# latch5.net
KiCad netlist of a schematic drawn in EAGLE
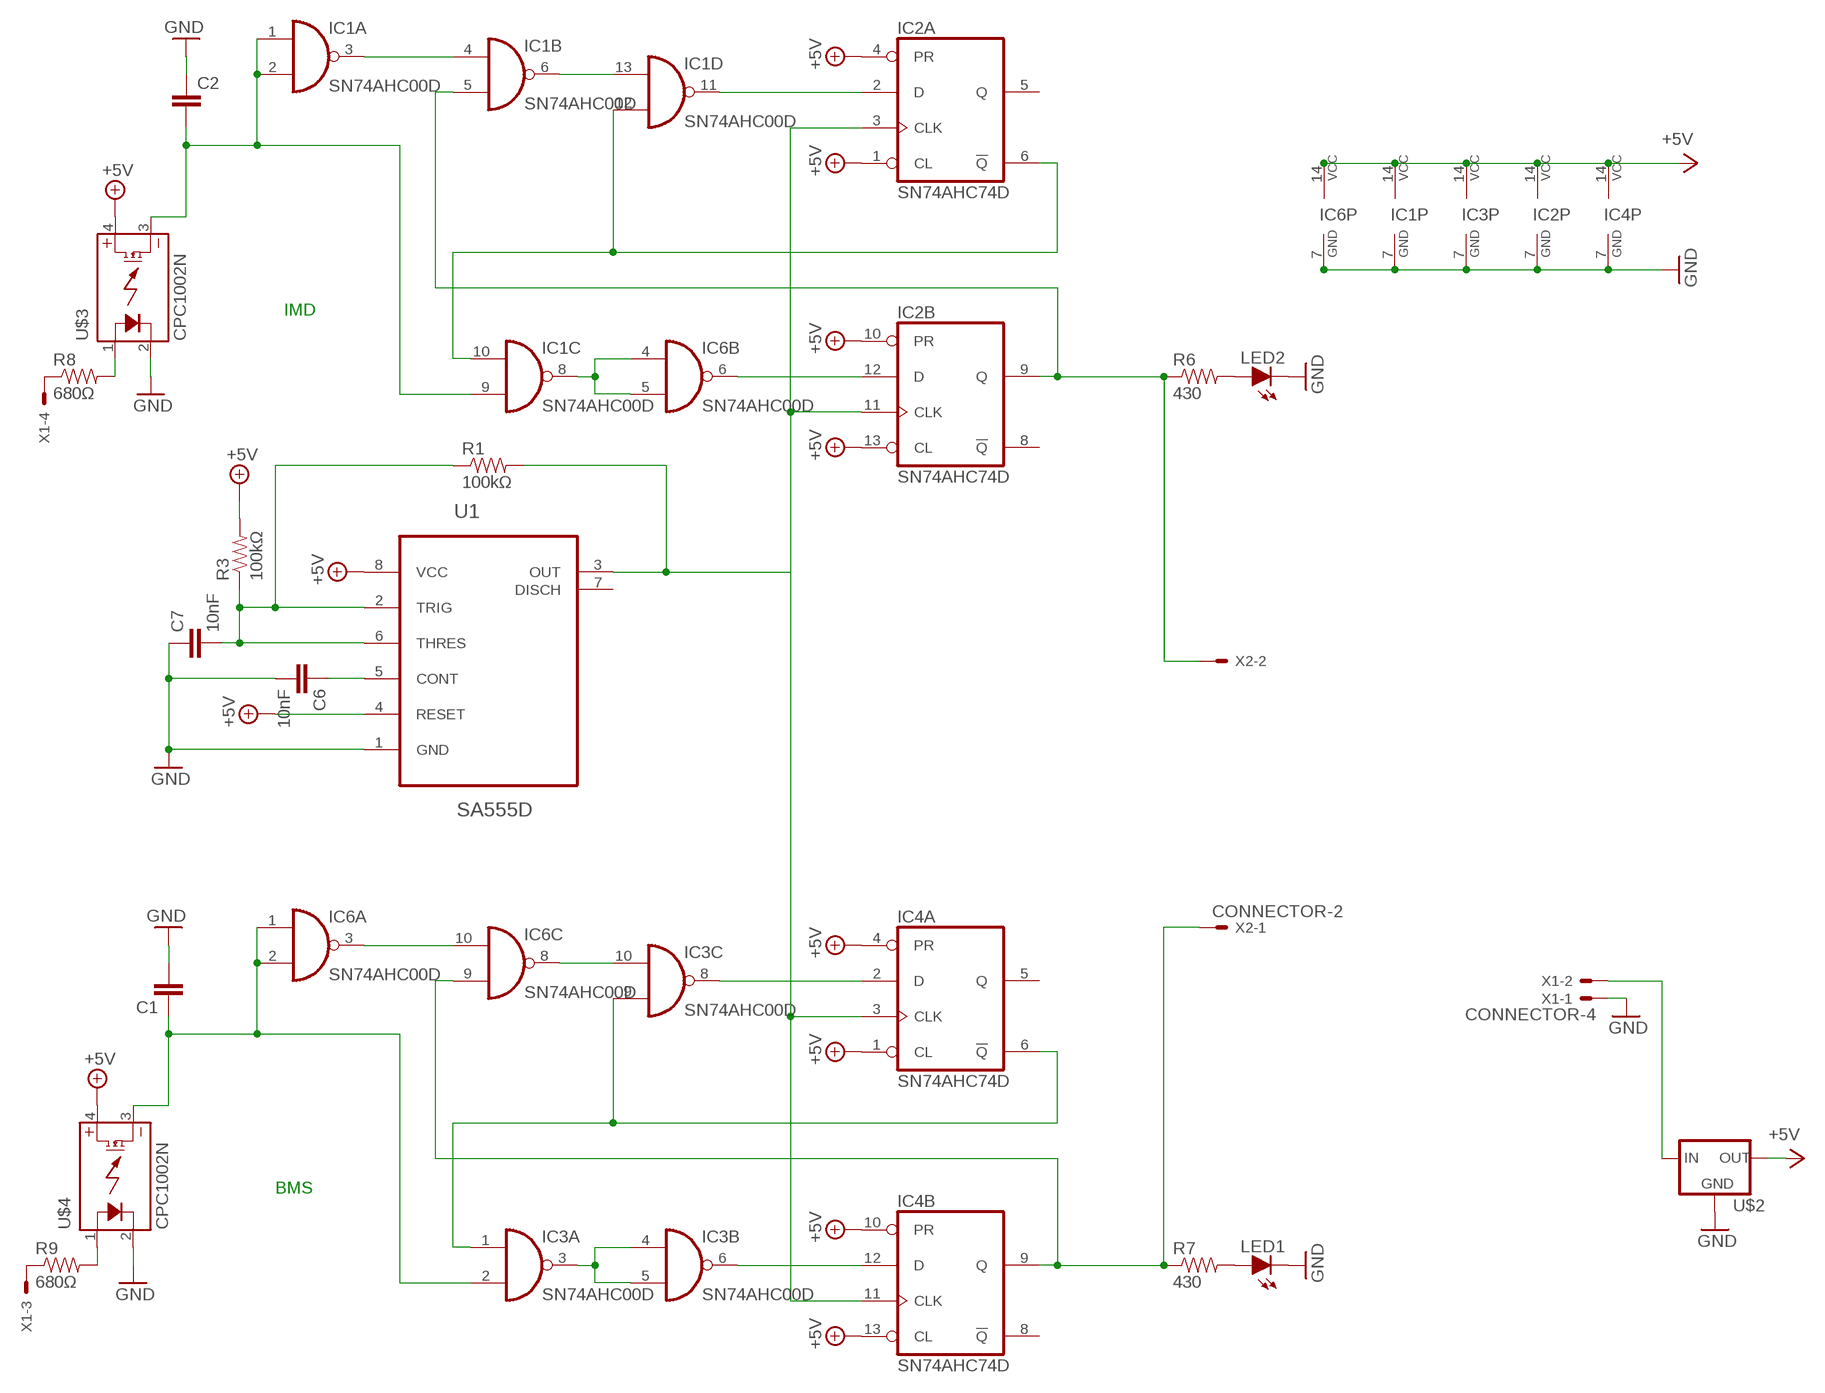
[diagram p0: schematic, sheet 1]

(export (version "E")
  (design (tool "Eeschema 10.0.6"))
  (components
    (comp (ref "C1")
      (value "CAP0402-CAP")
      (footprint "eagle-import:0402-CAP")
      (libsource (lib "eagle-import") (part "CAP0402-CAP"))
    )
    (comp (ref "C2")
      (value "CAP0402-CAP")
      (footprint "eagle-import:0402-CAP")
      (libsource (lib "eagle-import") (part "CAP0402-CAP"))
    )
    (comp (ref "C6")
      (value "10nF")
      (footprint "eagle-import:0402-CAP")
      (libsource (lib "eagle-import") (part "CAP0402-CAP"))
    )
    (comp (ref "C7")
      (value "10nF")
      (footprint "eagle-import:0402-CAP")
      (libsource (lib "eagle-import") (part "CAP0402-CAP"))
    )
    (comp (ref "IC1")
      (value "SN74AHC00D")
      (footprint "eagle-import:SOIC-14")
      (libsource (lib "eagle-import") (part "SN74AHC00D"))
    )
    (comp (ref "IC2")
      (value "SN74AHC74D")
      (footprint "eagle-import:SOIC-14")
      (libsource (lib "eagle-import") (part "SN74AHC74D"))
    )
    (comp (ref "IC3")
      (value "SN74AHC00D")
      (footprint "eagle-import:SOIC-14")
      (libsource (lib "eagle-import") (part "SN74AHC00D"))
    )
    (comp (ref "IC4")
      (value "SN74AHC74D")
      (footprint "eagle-import:SOIC-14")
      (libsource (lib "eagle-import") (part "SN74AHC74D"))
    )
    (comp (ref "IC6")
      (value "SN74AHC00D")
      (footprint "eagle-import:SOIC-14")
      (libsource (lib "eagle-import") (part "SN74AHC00D"))
    )
    (comp (ref "LED1")
      (value "LED-0805")
      (footprint "eagle-import:LED-805")
      (libsource (lib "eagle-import") (part "LED-0805"))
    )
    (comp (ref "LED2")
      (value "LED-0805")
      (footprint "eagle-import:LED-805")
      (libsource (lib "eagle-import") (part "LED-0805"))
    )
    (comp (ref "R1")
      (value "100kΩ")
      (footprint "eagle-import:0402-RES")
      (libsource (lib "eagle-import") (part "RESISTOR0402"))
    )
    (comp (ref "R3")
      (value "100kΩ")
      (footprint "eagle-import:0402-RES")
      (libsource (lib "eagle-import") (part "RESISTOR0402"))
    )
    (comp (ref "R6")
      (value "430")
      (footprint "eagle-import:0402-RES")
      (libsource (lib "eagle-import") (part "RESISTOR0402"))
    )
    (comp (ref "R7")
      (value "430")
      (footprint "eagle-import:0402-RES")
      (libsource (lib "eagle-import") (part "RESISTOR0402"))
    )
    (comp (ref "R8")
      (value "680Ω")
      (footprint "eagle-import:0402-RES")
      (libsource (lib "eagle-import") (part "RESISTOR0402"))
    )
    (comp (ref "R9")
      (value "680Ω")
      (footprint "eagle-import:0402-RES")
      (libsource (lib "eagle-import") (part "RESISTOR0402"))
    )
    (comp (ref "U$2")
      (value "5VREG_LM340-NLM340MPX-5.0/NOPB")
      (footprint "eagle-import:SOT223")
      (libsource (lib "eagle-import") (part "5VREG_LM340-NLM340MPX-5.0/NOPB"))
    )
    (comp (ref "U$3")
      (value "CPC1002N")
      (footprint "eagle-import:SOP04")
      (libsource (lib "eagle-import") (part "CPC1002N"))
    )
    (comp (ref "U$4")
      (value "CPC1002N")
      (footprint "eagle-import:SOP04")
      (libsource (lib "eagle-import") (part "CPC1002N"))
    )
    (comp (ref "U1")
      (value "SA555D")
      (footprint "eagle-import:SOIC127P600X175-8N")
      (libsource (lib "eagle-import") (part "SA555D"))
    )
    (comp (ref "X1")
      (value "CONNECTOR-4")
      (footprint "eagle-import:MINIFIT_5566-4")
      (libsource (lib "eagle-import") (part "CONNECTOR-4"))
    )
    (comp (ref "X2")
      (value "CONNECTOR-2")
      (footprint "eagle-import:MINIFIT_5566-2")
      (libsource (lib "eagle-import") (part "CONNECTOR-2"))
    )
  )
  (nets
    (net (code "1") (name "+5V") (class "Default")
      (node (ref "IC1") (pin "14") (pinfunction "VCC_14") (pintype "power_in"))
      (node (ref "IC2") (pin "1") (pinfunction "CL_1") (pintype "input"))
      (node (ref "IC2") (pin "10") (pinfunction "PR_10") (pintype "input"))
      (node (ref "IC2") (pin "13") (pinfunction "CL_13") (pintype "input"))
      (node (ref "IC2") (pin "14") (pinfunction "VCC_14") (pintype "power_in"))
      (node (ref "IC2") (pin "4") (pinfunction "PR_4") (pintype "input"))
      (node (ref "IC3") (pin "14") (pinfunction "VCC_14") (pintype "power_in"))
      (node (ref "IC4") (pin "1") (pinfunction "CL_1") (pintype "input"))
      (node (ref "IC4") (pin "10") (pinfunction "PR_10") (pintype "input"))
      (node (ref "IC4") (pin "13") (pinfunction "CL_13") (pintype "input"))
      (node (ref "IC4") (pin "14") (pinfunction "VCC_14") (pintype "power_in"))
      (node (ref "IC4") (pin "4") (pinfunction "PR_4") (pintype "input"))
      (node (ref "IC6") (pin "14") (pinfunction "VCC_14") (pintype "power_in"))
      (node (ref "R3") (pin "2") (pinfunction "2_2") (pintype "passive"))
      (node (ref "U$2") (pin "3") (pinfunction "OUT_3") (pintype "output"))
      (node (ref "U$3") (pin "4") (pinfunction "DC+_4") (pintype "passive"))
      (node (ref "U$4") (pin "4") (pinfunction "DC+_4") (pintype "passive"))
      (node (ref "U1") (pin "4") (pinfunction "RESET_4") (pintype "input"))
      (node (ref "U1") (pin "8") (pinfunction "VCC_8") (pintype "power_in"))
    )
    (net (code "2") (name "GND") (class "Default")
      (node (ref "C1") (pin "2") (pinfunction "2_2") (pintype "passive"))
      (node (ref "C2") (pin "1") (pinfunction "1_1") (pintype "passive"))
      (node (ref "C6") (pin "2") (pinfunction "2_2") (pintype "passive"))
      (node (ref "C7") (pin "1") (pinfunction "1_1") (pintype "passive"))
      (node (ref "IC1") (pin "7") (pinfunction "GND_7") (pintype "power_in"))
      (node (ref "IC2") (pin "7") (pinfunction "GND_7") (pintype "power_in"))
      (node (ref "IC3") (pin "7") (pinfunction "GND_7") (pintype "power_in"))
      (node (ref "IC4") (pin "7") (pinfunction "GND_7") (pintype "power_in"))
      (node (ref "IC6") (pin "7") (pinfunction "GND_7") (pintype "power_in"))
      (node (ref "LED1") (pin "C") (pinfunction "C_C") (pintype "passive"))
      (node (ref "LED2") (pin "C") (pinfunction "C_C") (pintype "passive"))
      (node (ref "U$2") (pin "2") (pinfunction "GND_2") (pintype "input"))
      (node (ref "U$2") (pin "4") (pinfunction "GND_4") (pintype "input"))
      (node (ref "U$3") (pin "2") (pinfunction "CONTROL-_2") (pintype "passive"))
      (node (ref "U$4") (pin "2") (pinfunction "CONTROL-_2") (pintype "passive"))
      (node (ref "U1") (pin "1") (pinfunction "GND_1") (pintype "passive"))
      (node (ref "X1") (pin "1") (pinfunction "S_1") (pintype "passive"))
    )
    (net (code "3") (name "Net-(IC1A-I0)") (class "Default")
      (node (ref "C2") (pin "2") (pinfunction "2_2") (pintype "passive"))
      (node (ref "IC1") (pin "1") (pinfunction "I0_1") (pintype "input"))
      (node (ref "IC1") (pin "2") (pinfunction "I1_2") (pintype "input"))
      (node (ref "IC1") (pin "9") (pinfunction "I1_9") (pintype "input"))
      (node (ref "U$3") (pin "3") (pinfunction "DC-_3") (pintype "passive"))
    )
    (net (code "4") (name "Net-(IC1A-O)") (class "Default")
      (node (ref "IC1") (pin "3") (pinfunction "O_3") (pintype "output"))
      (node (ref "IC1") (pin "4") (pinfunction "I0_4") (pintype "input"))
    )
    (net (code "5") (name "Net-(IC1B-I1)") (class "Default")
      (node (ref "IC1") (pin "5") (pinfunction "I1_5") (pintype "input"))
      (node (ref "IC2") (pin "9") (pinfunction "Q_9") (pintype "output"))
      (node (ref "R6") (pin "1") (pinfunction "1_1") (pintype "passive"))
      (node (ref "X2") (pin "2") (pinfunction "S_2") (pintype "passive"))
    )
    (net (code "6") (name "Net-(IC1B-O)") (class "Default")
      (node (ref "IC1") (pin "13") (pinfunction "I0_13") (pintype "input"))
      (node (ref "IC1") (pin "6") (pinfunction "O_6") (pintype "output"))
    )
    (net (code "7") (name "Net-(IC1C-I0)") (class "Default")
      (node (ref "IC1") (pin "10") (pinfunction "I0_10") (pintype "input"))
      (node (ref "IC1") (pin "12") (pinfunction "I1_12") (pintype "input"))
      (node (ref "IC2") (pin "6") (pinfunction "~{Q}_6") (pintype "output"))
    )
    (net (code "8") (name "Net-(IC1C-O)") (class "Default")
      (node (ref "IC1") (pin "8") (pinfunction "O_8") (pintype "output"))
      (node (ref "IC6") (pin "4") (pinfunction "I0_4") (pintype "input"))
      (node (ref "IC6") (pin "5") (pinfunction "I1_5") (pintype "input"))
    )
    (net (code "9") (name "Net-(IC1D-O)") (class "Default")
      (node (ref "IC1") (pin "11") (pinfunction "O_11") (pintype "output"))
      (node (ref "IC2") (pin "2") (pinfunction "D_2") (pintype "input"))
    )
    (net (code "10") (name "Net-(IC2A-CLK)") (class "Default")
      (node (ref "IC2") (pin "11") (pinfunction "CLK_11") (pintype "input"))
      (node (ref "IC2") (pin "3") (pinfunction "CLK_3") (pintype "input"))
      (node (ref "IC4") (pin "11") (pinfunction "CLK_11") (pintype "input"))
      (node (ref "IC4") (pin "3") (pinfunction "CLK_3") (pintype "input"))
      (node (ref "R1") (pin "2") (pinfunction "2_2") (pintype "passive"))
      (node (ref "U1") (pin "3") (pinfunction "OUT_3") (pintype "output"))
    )
    (net (code "11") (name "Net-(IC2B-D)") (class "Default")
      (node (ref "IC2") (pin "12") (pinfunction "D_12") (pintype "input"))
      (node (ref "IC6") (pin "6") (pinfunction "O_6") (pintype "output"))
    )
    (net (code "12") (name "Net-(IC3A-I0)") (class "Default")
      (node (ref "IC3") (pin "1") (pinfunction "I0_1") (pintype "input"))
      (node (ref "IC3") (pin "9") (pinfunction "I1_9") (pintype "input"))
      (node (ref "IC4") (pin "6") (pinfunction "~{Q}_6") (pintype "output"))
    )
    (net (code "13") (name "Net-(IC3A-I1)") (class "Default")
      (node (ref "C1") (pin "1") (pinfunction "1_1") (pintype "passive"))
      (node (ref "IC3") (pin "2") (pinfunction "I1_2") (pintype "input"))
      (node (ref "IC6") (pin "1") (pinfunction "I0_1") (pintype "input"))
      (node (ref "IC6") (pin "2") (pinfunction "I1_2") (pintype "input"))
      (node (ref "U$4") (pin "3") (pinfunction "DC-_3") (pintype "passive"))
    )
    (net (code "14") (name "Net-(IC3A-O)") (class "Default")
      (node (ref "IC3") (pin "3") (pinfunction "O_3") (pintype "output"))
      (node (ref "IC3") (pin "4") (pinfunction "I0_4") (pintype "input"))
      (node (ref "IC3") (pin "5") (pinfunction "I1_5") (pintype "input"))
    )
    (net (code "15") (name "Net-(IC3B-O)") (class "Default")
      (node (ref "IC3") (pin "6") (pinfunction "O_6") (pintype "output"))
      (node (ref "IC4") (pin "12") (pinfunction "D_12") (pintype "input"))
    )
    (net (code "16") (name "Net-(IC3C-I0)") (class "Default")
      (node (ref "IC3") (pin "10") (pinfunction "I0_10") (pintype "input"))
      (node (ref "IC6") (pin "8") (pinfunction "O_8") (pintype "output"))
    )
    (net (code "17") (name "Net-(IC3C-O)") (class "Default")
      (node (ref "IC3") (pin "8") (pinfunction "O_8") (pintype "output"))
      (node (ref "IC4") (pin "2") (pinfunction "D_2") (pintype "input"))
    )
    (net (code "18") (name "Net-(IC4B-Q)") (class "Default")
      (node (ref "IC4") (pin "9") (pinfunction "Q_9") (pintype "output"))
      (node (ref "IC6") (pin "9") (pinfunction "I1_9") (pintype "input"))
      (node (ref "R7") (pin "1") (pinfunction "1_1") (pintype "passive"))
      (node (ref "X2") (pin "1") (pinfunction "S_1") (pintype "passive"))
    )
    (net (code "19") (name "Net-(IC6A-O)") (class "Default")
      (node (ref "IC6") (pin "10") (pinfunction "I0_10") (pintype "input"))
      (node (ref "IC6") (pin "3") (pinfunction "O_3") (pintype "output"))
    )
    (net (code "20") (name "Net-(LED1-PadA)") (class "Default")
      (node (ref "LED1") (pin "A") (pinfunction "A_A") (pintype "passive"))
      (node (ref "R7") (pin "2") (pinfunction "2_2") (pintype "passive"))
    )
    (net (code "21") (name "Net-(LED2-PadA)") (class "Default")
      (node (ref "LED2") (pin "A") (pinfunction "A_A") (pintype "passive"))
      (node (ref "R6") (pin "2") (pinfunction "2_2") (pintype "passive"))
    )
    (net (code "22") (name "Net-(U$2-IN)") (class "Default")
      (node (ref "U$2") (pin "1") (pinfunction "IN_1") (pintype "input"))
      (node (ref "X1") (pin "2") (pinfunction "S_2") (pintype "passive"))
    )
    (net (code "23") (name "Net-(U$3-CONTROL+)") (class "Default")
      (node (ref "R8") (pin "2") (pinfunction "2_2") (pintype "passive"))
      (node (ref "U$3") (pin "1") (pinfunction "CONTROL+_1") (pintype "passive"))
    )
    (net (code "24") (name "Net-(U$4-CONTROL+)") (class "Default")
      (node (ref "R9") (pin "2") (pinfunction "2_2") (pintype "passive"))
      (node (ref "U$4") (pin "1") (pinfunction "CONTROL+_1") (pintype "passive"))
    )
    (net (code "25") (name "Net-(U1-CONT)") (class "Default")
      (node (ref "C6") (pin "1") (pinfunction "1_1") (pintype "passive"))
      (node (ref "U1") (pin "5") (pinfunction "CONT_5") (pintype "input"))
    )
    (net (code "26") (name "Net-(U1-THRES)") (class "Default")
      (node (ref "C7") (pin "2") (pinfunction "2_2") (pintype "passive"))
      (node (ref "R1") (pin "1") (pinfunction "1_1") (pintype "passive"))
      (node (ref "R3") (pin "1") (pinfunction "1_1") (pintype "passive"))
      (node (ref "U1") (pin "2") (pinfunction "TRIG_2") (pintype "input"))
      (node (ref "U1") (pin "6") (pinfunction "THRES_6") (pintype "input"))
    )
    (net (code "27") (name "Net-(X1C-S)") (class "Default")
      (node (ref "R9") (pin "1") (pinfunction "1_1") (pintype "passive"))
      (node (ref "X1") (pin "3") (pinfunction "S_3") (pintype "passive"))
    )
    (net (code "28") (name "Net-(X1D-S)") (class "Default")
      (node (ref "R8") (pin "1") (pinfunction "1_1") (pintype "passive"))
      (node (ref "X1") (pin "4") (pinfunction "S_4") (pintype "passive"))
    )
    (net (code "29") (name "unconnected-(IC2A-Q-Pad5)") (class "Default")
      (node (ref "IC2") (pin "5") (pinfunction "Q_5") (pintype "output"))
    )
    (net (code "30") (name "unconnected-(IC2B-~{Q}-Pad8)") (class "Default")
      (node (ref "IC2") (pin "8") (pinfunction "~{Q}_8") (pintype "output"))
    )
    (net (code "31") (name "unconnected-(IC4A-Q-Pad5)") (class "Default")
      (node (ref "IC4") (pin "5") (pinfunction "Q_5") (pintype "output"))
    )
    (net (code "32") (name "unconnected-(IC4B-~{Q}-Pad8)") (class "Default")
      (node (ref "IC4") (pin "8") (pinfunction "~{Q}_8") (pintype "output"))
    )
    (net (code "33") (name "unconnected-(U1-DISCH-Pad7)") (class "Default")
      (node (ref "U1") (pin "7") (pinfunction "DISCH_7") (pintype "output"))
    )
  )
)
